# eagle65brdfile.net
KiCad netlist of a schematic drawn in EAGLE
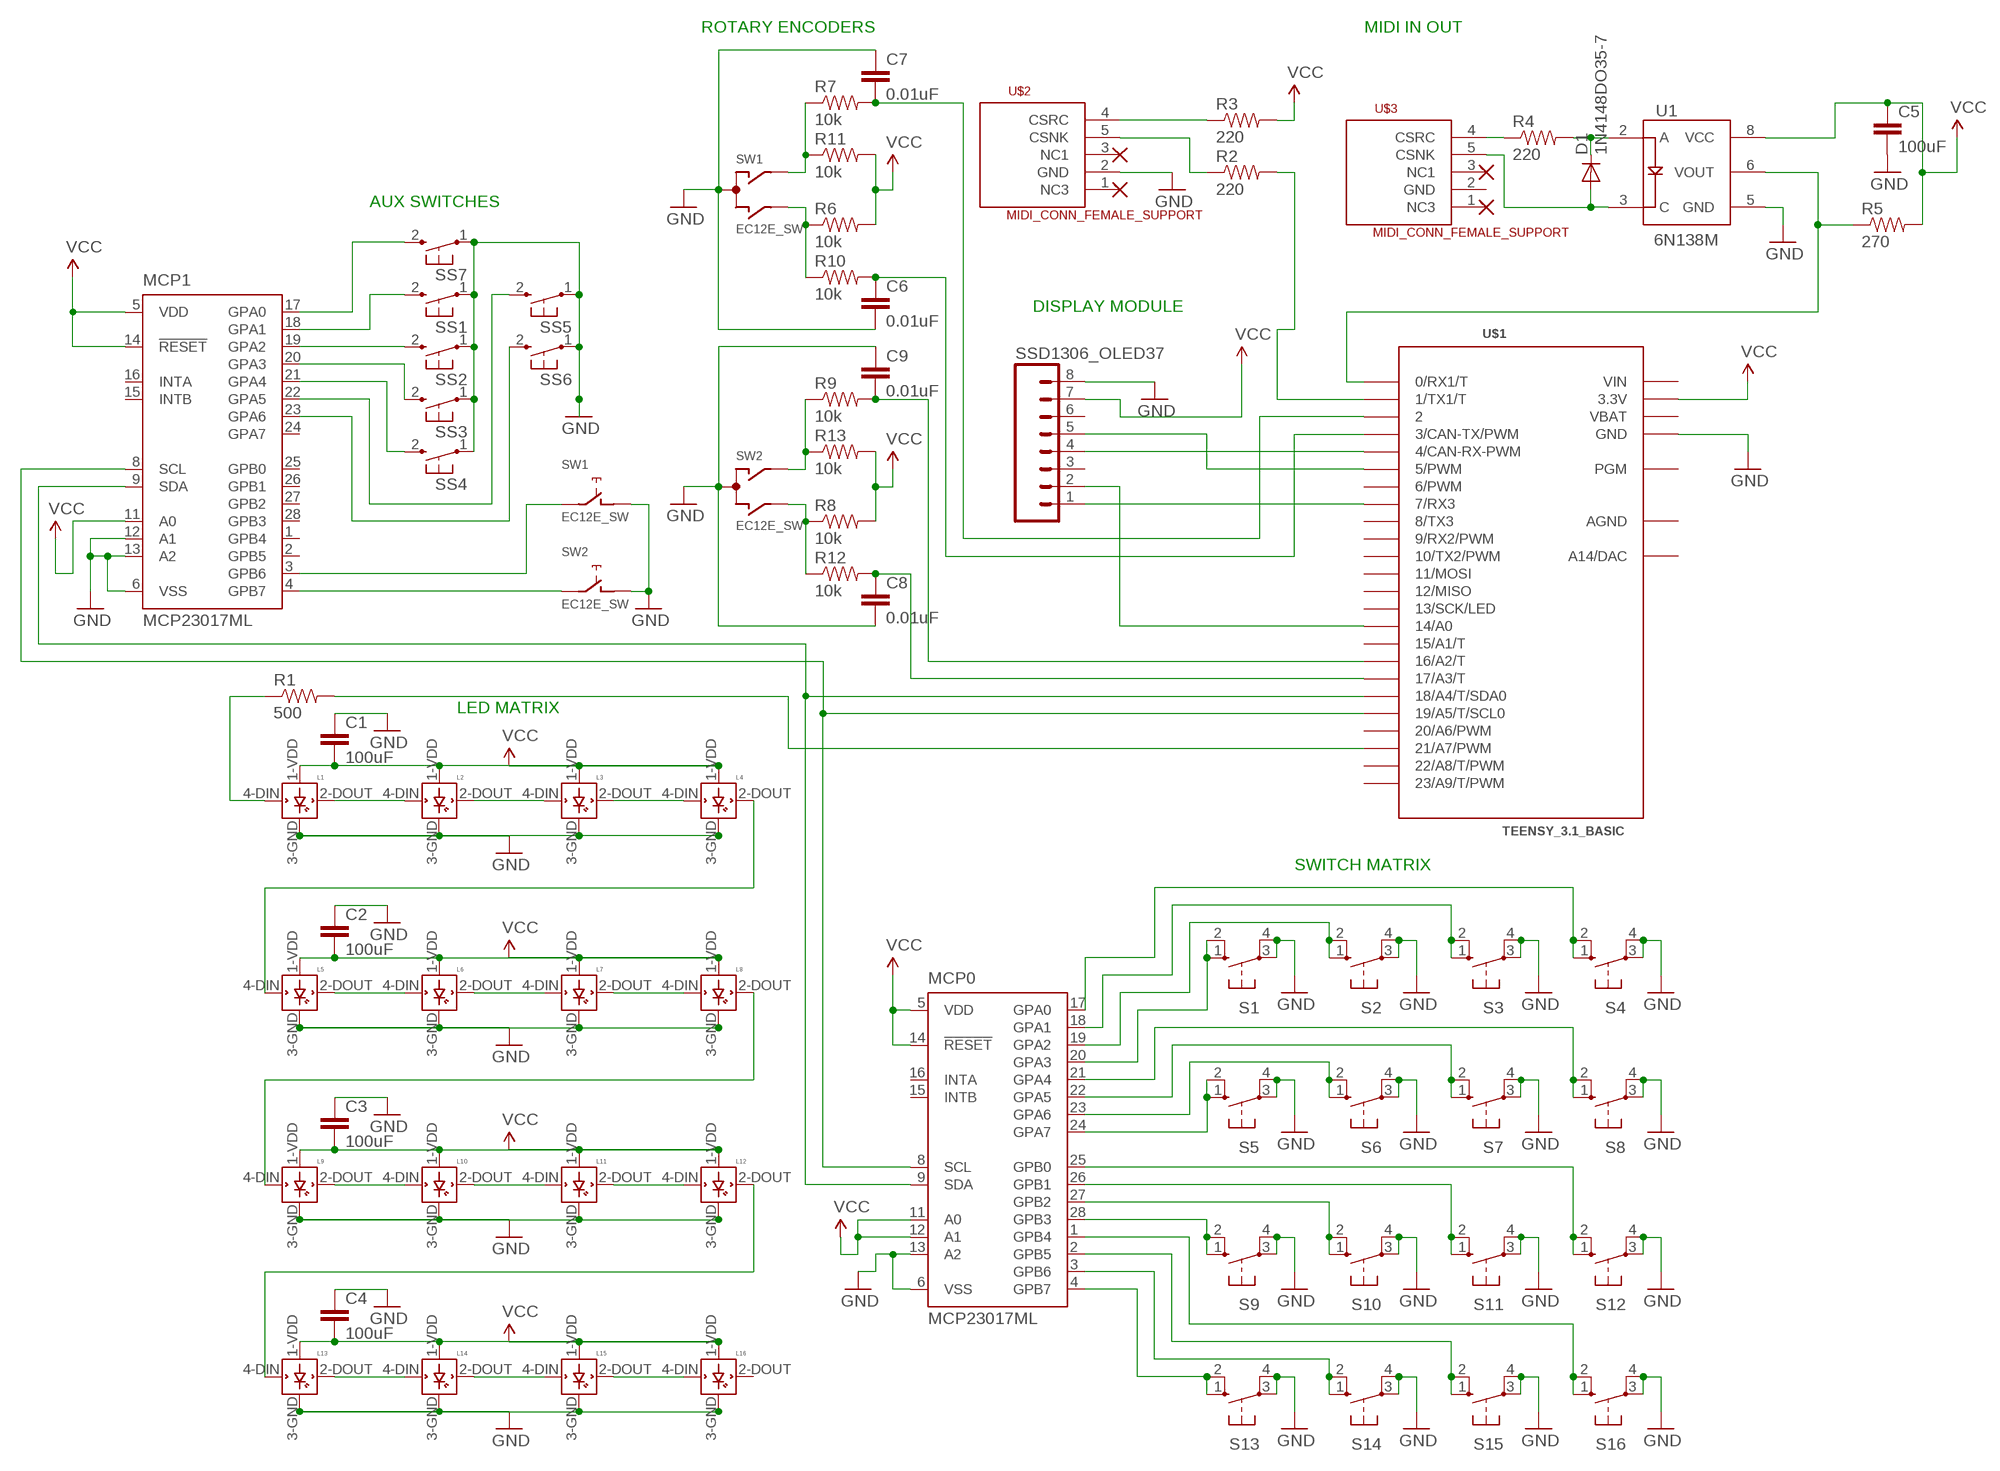
[diagram p0: schematic, sheet 1]

(export (version "E")
  (design (tool "Eeschema 10.0.6"))
  (components
    (comp (ref "C1")
      (value "100uF")
      (footprint "eagle-import:0805")
      (libsource (lib "eagle-import") (part "1.0UF-25V-+80/-20(0805)"))
    )
    (comp (ref "C2")
      (value "100uF")
      (footprint "eagle-import:0805")
      (libsource (lib "eagle-import") (part "1.0UF-25V-+80/-20(0805)"))
    )
    (comp (ref "C3")
      (value "100uF")
      (footprint "eagle-import:0805")
      (libsource (lib "eagle-import") (part "1.0UF-25V-+80/-20(0805)"))
    )
    (comp (ref "C4")
      (value "100uF")
      (footprint "eagle-import:0805")
      (libsource (lib "eagle-import") (part "1.0UF-25V-+80/-20(0805)"))
    )
    (comp (ref "C5")
      (value "100uF")
      (footprint "eagle-import:0805")
      (libsource (lib "eagle-import") (part "1.0UF-25V-+80/-20(0805)"))
    )
    (comp (ref "C6")
      (value "0.01uF")
      (footprint "eagle-import:0805")
      (libsource (lib "eagle-import") (part "1.0UF-25V-+80/-20(0805)"))
    )
    (comp (ref "C7")
      (value "0.01uF")
      (footprint "eagle-import:0805")
      (libsource (lib "eagle-import") (part "1.0UF-25V-+80/-20(0805)"))
    )
    (comp (ref "C8")
      (value "0.01uF")
      (footprint "eagle-import:0805")
      (libsource (lib "eagle-import") (part "1.0UF-25V-+80/-20(0805)"))
    )
    (comp (ref "C9")
      (value "0.01uF")
      (footprint "eagle-import:0805")
      (libsource (lib "eagle-import") (part "1.0UF-25V-+80/-20(0805)"))
    )
    (comp (ref "D1")
      (value "1N4148DO35-7")
      (footprint "eagle-import:DO35-7")
      (libsource (lib "eagle-import") (part "1N4148DO35-7"))
    )
    (comp (ref "L1")
      (value "WS2812B")
      (footprint "eagle-import:WS2812B")
      (libsource (lib "eagle-import") (part "WS2812B"))
    )
    (comp (ref "L2")
      (value "WS2812B")
      (footprint "eagle-import:WS2812B")
      (libsource (lib "eagle-import") (part "WS2812B"))
    )
    (comp (ref "L3")
      (value "WS2812B")
      (footprint "eagle-import:WS2812B")
      (libsource (lib "eagle-import") (part "WS2812B"))
    )
    (comp (ref "L4")
      (value "WS2812B")
      (footprint "eagle-import:WS2812B")
      (libsource (lib "eagle-import") (part "WS2812B"))
    )
    (comp (ref "L5")
      (value "WS2812B")
      (footprint "eagle-import:WS2812B")
      (libsource (lib "eagle-import") (part "WS2812B"))
    )
    (comp (ref "L6")
      (value "WS2812B")
      (footprint "eagle-import:WS2812B")
      (libsource (lib "eagle-import") (part "WS2812B"))
    )
    (comp (ref "L7")
      (value "WS2812B")
      (footprint "eagle-import:WS2812B")
      (libsource (lib "eagle-import") (part "WS2812B"))
    )
    (comp (ref "L8")
      (value "WS2812B")
      (footprint "eagle-import:WS2812B")
      (libsource (lib "eagle-import") (part "WS2812B"))
    )
    (comp (ref "L9")
      (value "WS2812B")
      (footprint "eagle-import:WS2812B")
      (libsource (lib "eagle-import") (part "WS2812B"))
    )
    (comp (ref "L10")
      (value "WS2812B")
      (footprint "eagle-import:WS2812B")
      (libsource (lib "eagle-import") (part "WS2812B"))
    )
    (comp (ref "L11")
      (value "WS2812B")
      (footprint "eagle-import:WS2812B")
      (libsource (lib "eagle-import") (part "WS2812B"))
    )
    (comp (ref "L12")
      (value "WS2812B")
      (footprint "eagle-import:WS2812B")
      (libsource (lib "eagle-import") (part "WS2812B"))
    )
    (comp (ref "L13")
      (value "WS2812B")
      (footprint "eagle-import:WS2812B")
      (libsource (lib "eagle-import") (part "WS2812B"))
    )
    (comp (ref "L14")
      (value "WS2812B")
      (footprint "eagle-import:WS2812B")
      (libsource (lib "eagle-import") (part "WS2812B"))
    )
    (comp (ref "L15")
      (value "WS2812B")
      (footprint "eagle-import:WS2812B")
      (libsource (lib "eagle-import") (part "WS2812B"))
    )
    (comp (ref "L16")
      (value "WS2812B")
      (footprint "eagle-import:WS2812B")
      (libsource (lib "eagle-import") (part "WS2812B"))
    )
    (comp (ref "MCP0")
      (value "MCP23017ML")
      (footprint "eagle-import:QFN28-ML_6X6MM")
      (fields (field (name "MF") "MICROCHIP") (field (name "MPN") "MCP23017-E/ML"))
      (libsource (lib "eagle-import") (part "MCP23017ML"))
    )
    (comp (ref "MCP1")
      (value "MCP23017ML")
      (footprint "eagle-import:QFN28-ML_6X6MM")
      (fields (field (name "MF") "MICROCHIP") (field (name "MPN") "MCP23017-E/ML"))
      (libsource (lib "eagle-import") (part "MCP23017ML"))
    )
    (comp (ref "R1")
      (value "500")
      (footprint "eagle-import:0805")
      (libsource (lib "eagle-import") (part "RESISTOR0805-RES"))
    )
    (comp (ref "R2")
      (value "220")
      (footprint "eagle-import:0805")
      (libsource (lib "eagle-import") (part "RESISTOR0805-RES"))
    )
    (comp (ref "R3")
      (value "220")
      (footprint "eagle-import:0805")
      (libsource (lib "eagle-import") (part "RESISTOR0805-RES"))
    )
    (comp (ref "R4")
      (value "220")
      (footprint "eagle-import:0805")
      (libsource (lib "eagle-import") (part "RESISTOR0805-RES"))
    )
    (comp (ref "R5")
      (value "270")
      (footprint "eagle-import:0805")
      (libsource (lib "eagle-import") (part "RESISTOR0805-RES"))
    )
    (comp (ref "R6")
      (value "10k")
      (footprint "eagle-import:0805")
      (libsource (lib "eagle-import") (part "RESISTOR0805-RES"))
    )
    (comp (ref "R7")
      (value "10k")
      (footprint "eagle-import:0805")
      (libsource (lib "eagle-import") (part "RESISTOR0805-RES"))
    )
    (comp (ref "R8")
      (value "10k")
      (footprint "eagle-import:0805")
      (libsource (lib "eagle-import") (part "RESISTOR0805-RES"))
    )
    (comp (ref "R9")
      (value "10k")
      (footprint "eagle-import:0805")
      (libsource (lib "eagle-import") (part "RESISTOR0805-RES"))
    )
    (comp (ref "R10")
      (value "10k")
      (footprint "eagle-import:0805")
      (libsource (lib "eagle-import") (part "RESISTOR0805-RES"))
    )
    (comp (ref "R11")
      (value "10k")
      (footprint "eagle-import:0805")
      (libsource (lib "eagle-import") (part "RESISTOR0805-RES"))
    )
    (comp (ref "R12")
      (value "10k")
      (footprint "eagle-import:0805")
      (libsource (lib "eagle-import") (part "RESISTOR0805-RES"))
    )
    (comp (ref "R13")
      (value "10k")
      (footprint "eagle-import:0805")
      (libsource (lib "eagle-import") (part "RESISTOR0805-RES"))
    )
    (comp (ref "S1")
      (value "10-XX")
      (footprint "eagle-import:B3F-10XX")
      (fields (field (name "MPN") "B3F-1000"))
      (libsource (lib "eagle-import") (part "10-XX"))
    )
    (comp (ref "S2")
      (value "10-XX")
      (footprint "eagle-import:B3F-10XX")
      (fields (field (name "MPN") "B3F-1000"))
      (libsource (lib "eagle-import") (part "10-XX"))
    )
    (comp (ref "S3")
      (value "10-XX")
      (footprint "eagle-import:B3F-10XX")
      (fields (field (name "MPN") "B3F-1000"))
      (libsource (lib "eagle-import") (part "10-XX"))
    )
    (comp (ref "S4")
      (value "10-XX")
      (footprint "eagle-import:B3F-10XX")
      (fields (field (name "MPN") "B3F-1000"))
      (libsource (lib "eagle-import") (part "10-XX"))
    )
    (comp (ref "S5")
      (value "10-XX")
      (footprint "eagle-import:B3F-10XX")
      (fields (field (name "MPN") "B3F-1000"))
      (libsource (lib "eagle-import") (part "10-XX"))
    )
    (comp (ref "S6")
      (value "10-XX")
      (footprint "eagle-import:B3F-10XX")
      (fields (field (name "MPN") "B3F-1000"))
      (libsource (lib "eagle-import") (part "10-XX"))
    )
    (comp (ref "S7")
      (value "10-XX")
      (footprint "eagle-import:B3F-10XX")
      (fields (field (name "MPN") "B3F-1000"))
      (libsource (lib "eagle-import") (part "10-XX"))
    )
    (comp (ref "S8")
      (value "10-XX")
      (footprint "eagle-import:B3F-10XX")
      (fields (field (name "MPN") "B3F-1000"))
      (libsource (lib "eagle-import") (part "10-XX"))
    )
    (comp (ref "S9")
      (value "10-XX")
      (footprint "eagle-import:B3F-10XX")
      (fields (field (name "MPN") "B3F-1000"))
      (libsource (lib "eagle-import") (part "10-XX"))
    )
    (comp (ref "S10")
      (value "10-XX")
      (footprint "eagle-import:B3F-10XX")
      (fields (field (name "MPN") "B3F-1000"))
      (libsource (lib "eagle-import") (part "10-XX"))
    )
    (comp (ref "S11")
      (value "10-XX")
      (footprint "eagle-import:B3F-10XX")
      (fields (field (name "MPN") "B3F-1000"))
      (libsource (lib "eagle-import") (part "10-XX"))
    )
    (comp (ref "S12")
      (value "10-XX")
      (footprint "eagle-import:B3F-10XX")
      (fields (field (name "MPN") "B3F-1000"))
      (libsource (lib "eagle-import") (part "10-XX"))
    )
    (comp (ref "S13")
      (value "10-XX")
      (footprint "eagle-import:B3F-10XX")
      (fields (field (name "MPN") "B3F-1000"))
      (libsource (lib "eagle-import") (part "10-XX"))
    )
    (comp (ref "S14")
      (value "10-XX")
      (footprint "eagle-import:B3F-10XX")
      (fields (field (name "MPN") "B3F-1000"))
      (libsource (lib "eagle-import") (part "10-XX"))
    )
    (comp (ref "S15")
      (value "10-XX")
      (footprint "eagle-import:B3F-10XX")
      (fields (field (name "MPN") "B3F-1000"))
      (libsource (lib "eagle-import") (part "10-XX"))
    )
    (comp (ref "S16")
      (value "10-XX")
      (footprint "eagle-import:B3F-10XX")
      (fields (field (name "MPN") "B3F-1000"))
      (libsource (lib "eagle-import") (part "10-XX"))
    )
    (comp (ref "SS1")
      (value "10-XX6MMSLIM")
      (footprint "eagle-import:B3F-10XX")
      (libsource (lib "eagle-import") (part "10-XX6MMSLIM"))
    )
    (comp (ref "SS2")
      (value "10-XX6MMSLIM")
      (footprint "eagle-import:B3F-10XX")
      (libsource (lib "eagle-import") (part "10-XX6MMSLIM"))
    )
    (comp (ref "SS3")
      (value "10-XX6MMSLIM")
      (footprint "eagle-import:B3F-10XX")
      (libsource (lib "eagle-import") (part "10-XX6MMSLIM"))
    )
    (comp (ref "SS4")
      (value "10-XX6MMSLIM")
      (footprint "eagle-import:B3F-10XX")
      (libsource (lib "eagle-import") (part "10-XX6MMSLIM"))
    )
    (comp (ref "SS5")
      (value "10-XX6MMSLIM")
      (footprint "eagle-import:B3F-10XX")
      (libsource (lib "eagle-import") (part "10-XX6MMSLIM"))
    )
    (comp (ref "SS6")
      (value "10-XX6MMSLIM")
      (footprint "eagle-import:B3F-10XX")
      (libsource (lib "eagle-import") (part "10-XX6MMSLIM"))
    )
    (comp (ref "SS7")
      (value "10-XX6MMSLIM")
      (footprint "eagle-import:B3F-10XX")
      (libsource (lib "eagle-import") (part "10-XX6MMSLIM"))
    )
    (comp (ref "SSD1306_OLED37")
      (value "M08")
      (footprint "eagle-import:1X08_ROUND")
      (libsource (lib "eagle-import") (part "M08"))
    )
    (comp (ref "SW1")
      (value "EC12E_SW")
      (footprint "eagle-import:ALPS_EC12E_SW")
      (fields (field (name "MPN") "EC12E2424407"))
      (libsource (lib "eagle-import") (part "EC12E_SW"))
    )
    (comp (ref "SW2")
      (value "EC12E_SW")
      (footprint "eagle-import:ALPS_EC12E_SW")
      (fields (field (name "MPN") "EC12E2424407"))
      (libsource (lib "eagle-import") (part "EC12E_SW"))
    )
    (comp (ref "U$1")
      (value "TEENSY_3.1_BASIC")
      (footprint "eagle-import:TEENSY_3.1_BASIC")
      (libsource (lib "eagle-import") (part "TEENSY_3.1_BASIC"))
    )
    (comp (ref "U$2")
      (value "MIDI_CONN_FEMALE_SUPPORT")
      (footprint "eagle-import:DIN_5_FEMALE_SUPPORT")
      (libsource (lib "eagle-import") (part "MIDI_CONN_FEMALE_SUPPORT"))
    )
    (comp (ref "U$3")
      (value "MIDI_CONN_FEMALE_SUPPORT")
      (footprint "eagle-import:DIN_5_FEMALE_SUPPORT")
      (libsource (lib "eagle-import") (part "MIDI_CONN_FEMALE_SUPPORT"))
    )
    (comp (ref "U1")
      (value "6N138M")
      (footprint "eagle-import:8-SMD")
      (libsource (lib "eagle-import") (part "OPTO_DARL_6N138S"))
    )
  )
  (nets
    (net (code "1") (name "/AGND") (class "Default")
      (node (ref "U$1") (pin "AGND") (pinfunction "AGND_AGND") (pintype "power_in"))
    )
    (net (code "2") (name "/VBAT") (class "Default")
      (node (ref "U$1") (pin "VBAT") (pinfunction "VBAT_VBAT") (pintype "power_in"))
    )
    (net (code "3") (name "/VIN") (class "Default")
      (node (ref "U$1") (pin "VIN") (pinfunction "VIN_VIN") (pintype "power_in"))
    )
    (net (code "4") (name "GND") (class "Default")
      (node (ref "C1") (pin "1") (pinfunction "1_1") (pintype "passive"))
      (node (ref "C2") (pin "1") (pinfunction "1_1") (pintype "passive"))
      (node (ref "C3") (pin "1") (pinfunction "1_1") (pintype "passive"))
      (node (ref "C4") (pin "1") (pinfunction "1_1") (pintype "passive"))
      (node (ref "C5") (pin "2") (pinfunction "2_2") (pintype "passive"))
      (node (ref "C6") (pin "2") (pinfunction "2_2") (pintype "passive"))
      (node (ref "C7") (pin "1") (pinfunction "1_1") (pintype "passive"))
      (node (ref "C8") (pin "2") (pinfunction "2_2") (pintype "passive"))
      (node (ref "C9") (pin "1") (pinfunction "1_1") (pintype "passive"))
      (node (ref "L1") (pin "3-GND") (pinfunction "GND_3-GND") (pintype "bidirectional"))
      (node (ref "L10") (pin "3-GND") (pinfunction "GND_3-GND") (pintype "bidirectional"))
      (node (ref "L11") (pin "3-GND") (pinfunction "GND_3-GND") (pintype "bidirectional"))
      (node (ref "L12") (pin "3-GND") (pinfunction "GND_3-GND") (pintype "bidirectional"))
      (node (ref "L13") (pin "3-GND") (pinfunction "GND_3-GND") (pintype "bidirectional"))
      (node (ref "L14") (pin "3-GND") (pinfunction "GND_3-GND") (pintype "bidirectional"))
      (node (ref "L15") (pin "3-GND") (pinfunction "GND_3-GND") (pintype "bidirectional"))
      (node (ref "L16") (pin "3-GND") (pinfunction "GND_3-GND") (pintype "bidirectional"))
      (node (ref "L2") (pin "3-GND") (pinfunction "GND_3-GND") (pintype "bidirectional"))
      (node (ref "L3") (pin "3-GND") (pinfunction "GND_3-GND") (pintype "bidirectional"))
      (node (ref "L4") (pin "3-GND") (pinfunction "GND_3-GND") (pintype "bidirectional"))
      (node (ref "L5") (pin "3-GND") (pinfunction "GND_3-GND") (pintype "bidirectional"))
      (node (ref "L6") (pin "3-GND") (pinfunction "GND_3-GND") (pintype "bidirectional"))
      (node (ref "L7") (pin "3-GND") (pinfunction "GND_3-GND") (pintype "bidirectional"))
      (node (ref "L8") (pin "3-GND") (pinfunction "GND_3-GND") (pintype "bidirectional"))
      (node (ref "L9") (pin "3-GND") (pinfunction "GND_3-GND") (pintype "bidirectional"))
      (node (ref "MCP0") (pin "13") (pinfunction "A2_13") (pintype "input"))
      (node (ref "MCP0") (pin "6") (pinfunction "VSS_6") (pintype "power_in"))
      (node (ref "MCP1") (pin "12") (pinfunction "A1_12") (pintype "input"))
      (node (ref "MCP1") (pin "13") (pinfunction "A2_13") (pintype "input"))
      (node (ref "MCP1") (pin "6") (pinfunction "VSS_6") (pintype "power_in"))
      (node (ref "S1") (pin "3") (pinfunction "P_3") (pintype "passive"))
      (node (ref "S1") (pin "4") (pinfunction "P1_4") (pintype "passive"))
      (node (ref "S10") (pin "3") (pinfunction "P_3") (pintype "passive"))
      (node (ref "S10") (pin "4") (pinfunction "P1_4") (pintype "passive"))
      (node (ref "S11") (pin "3") (pinfunction "P_3") (pintype "passive"))
      (node (ref "S11") (pin "4") (pinfunction "P1_4") (pintype "passive"))
      (node (ref "S12") (pin "3") (pinfunction "P_3") (pintype "passive"))
      (node (ref "S12") (pin "4") (pinfunction "P1_4") (pintype "passive"))
      (node (ref "S13") (pin "3") (pinfunction "P_3") (pintype "passive"))
      (node (ref "S13") (pin "4") (pinfunction "P1_4") (pintype "passive"))
      (node (ref "S14") (pin "3") (pinfunction "P_3") (pintype "passive"))
      (node (ref "S14") (pin "4") (pinfunction "P1_4") (pintype "passive"))
      (node (ref "S15") (pin "3") (pinfunction "P_3") (pintype "passive"))
      (node (ref "S15") (pin "4") (pinfunction "P1_4") (pintype "passive"))
      (node (ref "S16") (pin "3") (pinfunction "P_3") (pintype "passive"))
      (node (ref "S16") (pin "4") (pinfunction "P1_4") (pintype "passive"))
      (node (ref "S2") (pin "3") (pinfunction "P_3") (pintype "passive"))
      (node (ref "S2") (pin "4") (pinfunction "P1_4") (pintype "passive"))
      (node (ref "S3") (pin "3") (pinfunction "P_3") (pintype "passive"))
      (node (ref "S3") (pin "4") (pinfunction "P1_4") (pintype "passive"))
      (node (ref "S4") (pin "3") (pinfunction "P_3") (pintype "passive"))
      (node (ref "S4") (pin "4") (pinfunction "P1_4") (pintype "passive"))
      (node (ref "S5") (pin "3") (pinfunction "P_3") (pintype "passive"))
      (node (ref "S5") (pin "4") (pinfunction "P1_4") (pintype "passive"))
      (node (ref "S6") (pin "3") (pinfunction "P_3") (pintype "passive"))
      (node (ref "S6") (pin "4") (pinfunction "P1_4") (pintype "passive"))
      (node (ref "S7") (pin "3") (pinfunction "P_3") (pintype "passive"))
      (node (ref "S7") (pin "4") (pinfunction "P1_4") (pintype "passive"))
      (node (ref "S8") (pin "3") (pinfunction "P_3") (pintype "passive"))
      (node (ref "S8") (pin "4") (pinfunction "P1_4") (pintype "passive"))
      (node (ref "S9") (pin "3") (pinfunction "P_3") (pintype "passive"))
      (node (ref "S9") (pin "4") (pinfunction "P1_4") (pintype "passive"))
      (node (ref "SS1") (pin "1") (pinfunction "P1_1") (pintype "passive"))
      (node (ref "SS2") (pin "1") (pinfunction "P1_1") (pintype "passive"))
      (node (ref "SS3") (pin "1") (pinfunction "P1_1") (pintype "passive"))
      (node (ref "SS4") (pin "1") (pinfunction "P1_1") (pintype "passive"))
      (node (ref "SS5") (pin "1") (pinfunction "P1_1") (pintype "passive"))
      (node (ref "SS6") (pin "1") (pinfunction "P1_1") (pintype "passive"))
      (node (ref "SS7") (pin "1") (pinfunction "P1_1") (pintype "passive"))
      (node (ref "SSD1306_OLED37") (pin "8") (pinfunction "8_8") (pintype "passive"))
      (node (ref "SW1") (pin "C") (pinfunction "C_C") (pintype "passive"))
      (node (ref "SW1") (pin "D") (pinfunction "1_D") (pintype "passive"))
      (node (ref "SW2") (pin "C") (pinfunction "C_C") (pintype "passive"))
      (node (ref "SW2") (pin "D") (pinfunction "1_D") (pintype "passive"))
      (node (ref "U$1") (pin "GND") (pinfunction "GND_GND") (pintype "power_in"))
      (node (ref "U$1") (pin "GND1") (pinfunction "GND_GND1") (pintype "power_in"))
      (node (ref "U$2") (pin "2") (pinfunction "GND_2") (pintype "bidirectional"))
      (node (ref "U1") (pin "5") (pinfunction "GND_5") (pintype "bidirectional"))
    )
    (net (code "5") (name "Net-(C7-Pad2)") (class "Default")
      (node (ref "C7") (pin "2") (pinfunction "2_2") (pintype "passive"))
      (node (ref "R7") (pin "2") (pinfunction "2_2") (pintype "passive"))
      (node (ref "U$1") (pin "2") (pinfunction "2_2") (pintype "bidirectional"))
    )
    (net (code "6") (name "Net-(L1-DIN)") (class "Default")
      (node (ref "L1") (pin "4-DIN") (pinfunction "DIN_4-DIN") (pintype "input"))
      (node (ref "R1") (pin "1") (pinfunction "1_1") (pintype "passive"))
    )
    (net (code "7") (name "Net-(L1-DOUT)") (class "Default")
      (node (ref "L1") (pin "2-DOUT") (pinfunction "DOUT_2-DOUT") (pintype "output"))
      (node (ref "L2") (pin "4-DIN") (pinfunction "DIN_4-DIN") (pintype "input"))
    )
    (net (code "8") (name "Net-(L2-DOUT)") (class "Default")
      (node (ref "L2") (pin "2-DOUT") (pinfunction "DOUT_2-DOUT") (pintype "output"))
      (node (ref "L3") (pin "4-DIN") (pinfunction "DIN_4-DIN") (pintype "input"))
    )
    (net (code "9") (name "Net-(L3-DOUT)") (class "Default")
      (node (ref "L3") (pin "2-DOUT") (pinfunction "DOUT_2-DOUT") (pintype "output"))
      (node (ref "L4") (pin "4-DIN") (pinfunction "DIN_4-DIN") (pintype "input"))
    )
    (net (code "10") (name "Net-(L4-DOUT)") (class "Default")
      (node (ref "L4") (pin "2-DOUT") (pinfunction "DOUT_2-DOUT") (pintype "output"))
      (node (ref "L5") (pin "4-DIN") (pinfunction "DIN_4-DIN") (pintype "input"))
    )
    (net (code "11") (name "Net-(L5-DOUT)") (class "Default")
      (node (ref "L5") (pin "2-DOUT") (pinfunction "DOUT_2-DOUT") (pintype "output"))
      (node (ref "L6") (pin "4-DIN") (pinfunction "DIN_4-DIN") (pintype "input"))
    )
    (net (code "12") (name "Net-(L6-DOUT)") (class "Default")
      (node (ref "L6") (pin "2-DOUT") (pinfunction "DOUT_2-DOUT") (pintype "output"))
      (node (ref "L7") (pin "4-DIN") (pinfunction "DIN_4-DIN") (pintype "input"))
    )
    (net (code "13") (name "Net-(L7-DOUT)") (class "Default")
      (node (ref "L7") (pin "2-DOUT") (pinfunction "DOUT_2-DOUT") (pintype "output"))
      (node (ref "L8") (pin "4-DIN") (pinfunction "DIN_4-DIN") (pintype "input"))
    )
    (net (code "14") (name "Net-(L8-DOUT)") (class "Default")
      (node (ref "L8") (pin "2-DOUT") (pinfunction "DOUT_2-DOUT") (pintype "output"))
      (node (ref "L9") (pin "4-DIN") (pinfunction "DIN_4-DIN") (pintype "input"))
    )
    (net (code "15") (name "Net-(L10-DIN)") (class "Default")
      (node (ref "L10") (pin "4-DIN") (pinfunction "DIN_4-DIN") (pintype "input"))
      (node (ref "L9") (pin "2-DOUT") (pinfunction "DOUT_2-DOUT") (pintype "output"))
    )
    (net (code "16") (name "Net-(L10-DOUT)") (class "Default")
      (node (ref "L10") (pin "2-DOUT") (pinfunction "DOUT_2-DOUT") (pintype "output"))
      (node (ref "L11") (pin "4-DIN") (pinfunction "DIN_4-DIN") (pintype "input"))
    )
    (net (code "17") (name "Net-(L11-DOUT)") (class "Default")
      (node (ref "L11") (pin "2-DOUT") (pinfunction "DOUT_2-DOUT") (pintype "output"))
      (node (ref "L12") (pin "4-DIN") (pinfunction "DIN_4-DIN") (pintype "input"))
    )
    (net (code "18") (name "Net-(L12-DOUT)") (class "Default")
      (node (ref "L12") (pin "2-DOUT") (pinfunction "DOUT_2-DOUT") (pintype "output"))
      (node (ref "L13") (pin "4-DIN") (pinfunction "DIN_4-DIN") (pintype "input"))
    )
    (net (code "19") (name "Net-(L13-DOUT)") (class "Default")
      (node (ref "L13") (pin "2-DOUT") (pinfunction "DOUT_2-DOUT") (pintype "output"))
      (node (ref "L14") (pin "4-DIN") (pinfunction "DIN_4-DIN") (pintype "input"))
    )
    (net (code "20") (name "Net-(L14-DOUT)") (class "Default")
      (node (ref "L14") (pin "2-DOUT") (pinfunction "DOUT_2-DOUT") (pintype "output"))
      (node (ref "L15") (pin "4-DIN") (pinfunction "DIN_4-DIN") (pintype "input"))
    )
    (net (code "21") (name "Net-(L15-DOUT)") (class "Default")
      (node (ref "L15") (pin "2-DOUT") (pinfunction "DOUT_2-DOUT") (pintype "output"))
      (node (ref "L16") (pin "4-DIN") (pinfunction "DIN_4-DIN") (pintype "input"))
    )
    (net (code "22") (name "Net-(MCP0-GPA0)") (class "Default")
      (node (ref "MCP0") (pin "17") (pinfunction "GPA0_17") (pintype "bidirectional"))
      (node (ref "S4") (pin "1") (pinfunction "S_1") (pintype "passive"))
      (node (ref "S4") (pin "2") (pinfunction "S1_2") (pintype "passive"))
    )
    (net (code "23") (name "Net-(MCP0-GPA1)") (class "Default")
      (node (ref "MCP0") (pin "18") (pinfunction "GPA1_18") (pintype "bidirectional"))
      (node (ref "S3") (pin "1") (pinfunction "S_1") (pintype "passive"))
      (node (ref "S3") (pin "2") (pinfunction "S1_2") (pintype "passive"))
    )
    (net (code "24") (name "Net-(MCP0-GPA2)") (class "Default")
      (node (ref "MCP0") (pin "19") (pinfunction "GPA2_19") (pintype "bidirectional"))
      (node (ref "S2") (pin "1") (pinfunction "S_1") (pintype "passive"))
      (node (ref "S2") (pin "2") (pinfunction "S1_2") (pintype "passive"))
    )
    (net (code "25") (name "Net-(MCP0-GPA3)") (class "Default")
      (node (ref "MCP0") (pin "20") (pinfunction "GPA3_20") (pintype "bidirectional"))
      (node (ref "S1") (pin "1") (pinfunction "S_1") (pintype "passive"))
      (node (ref "S1") (pin "2") (pinfunction "S1_2") (pintype "passive"))
    )
    (net (code "26") (name "Net-(MCP0-GPA4)") (class "Default")
      (node (ref "MCP0") (pin "21") (pinfunction "GPA4_21") (pintype "bidirectional"))
      (node (ref "S8") (pin "1") (pinfunction "S_1") (pintype "passive"))
      (node (ref "S8") (pin "2") (pinfunction "S1_2") (pintype "passive"))
    )
    (net (code "27") (name "Net-(MCP0-GPA5)") (class "Default")
      (node (ref "MCP0") (pin "22") (pinfunction "GPA5_22") (pintype "bidirectional"))
      (node (ref "S7") (pin "1") (pinfunction "S_1") (pintype "passive"))
      (node (ref "S7") (pin "2") (pinfunction "S1_2") (pintype "passive"))
    )
    (net (code "28") (name "Net-(MCP0-GPA6)") (class "Default")
      (node (ref "MCP0") (pin "23") (pinfunction "GPA6_23") (pintype "bidirectional"))
      (node (ref "S6") (pin "1") (pinfunction "S_1") (pintype "passive"))
      (node (ref "S6") (pin "2") (pinfunction "S1_2") (pintype "passive"))
    )
    (net (code "29") (name "Net-(MCP0-GPA7)") (class "Default")
      (node (ref "MCP0") (pin "24") (pinfunction "GPA7_24") (pintype "bidirectional"))
      (node (ref "S5") (pin "1") (pinfunction "S_1") (pintype "passive"))
      (node (ref "S5") (pin "2") (pinfunction "S1_2") (pintype "passive"))
    )
    (net (code "30") (name "Net-(MCP0-GPB0)") (class "Default")
      (node (ref "MCP0") (pin "25") (pinfunction "GPB0_25") (pintype "bidirectional"))
      (node (ref "S12") (pin "1") (pinfunction "S_1") (pintype "passive"))
      (node (ref "S12") (pin "2") (pinfunction "S1_2") (pintype "passive"))
    )
    (net (code "31") (name "Net-(MCP0-GPB1)") (class "Default")
      (node (ref "MCP0") (pin "26") (pinfunction "GPB1_26") (pintype "bidirectional"))
      (node (ref "S11") (pin "1") (pinfunction "S_1") (pintype "passive"))
      (node (ref "S11") (pin "2") (pinfunction "S1_2") (pintype "passive"))
    )
    (net (code "32") (name "Net-(MCP0-GPB2)") (class "Default")
      (node (ref "MCP0") (pin "27") (pinfunction "GPB2_27") (pintype "bidirectional"))
      (node (ref "S10") (pin "1") (pinfunction "S_1") (pintype "passive"))
      (node (ref "S10") (pin "2") (pinfunction "S1_2") (pintype "passive"))
    )
    (net (code "33") (name "Net-(MCP0-GPB3)") (class "Default")
      (node (ref "MCP0") (pin "28") (pinfunction "GPB3_28") (pintype "bidirectional"))
      (node (ref "S9") (pin "1") (pinfunction "S_1") (pintype "passive"))
      (node (ref "S9") (pin "2") (pinfunction "S1_2") (pintype "passive"))
    )
    (net (code "34") (name "Net-(MCP0-GPB4)") (class "Default")
      (node (ref "MCP0") (pin "1") (pinfunction "GPB4_1") (pintype "bidirectional"))
      (node (ref "S16") (pin "1") (pinfunction "S_1") (pintype "passive"))
      (node (ref "S16") (pin "2") (pinfunction "S1_2") (pintype "passive"))
    )
    (net (code "35") (name "Net-(MCP0-GPB5)") (class "Default")
      (node (ref "MCP0") (pin "2") (pinfunction "GPB5_2") (pintype "bidirectional"))
      (node (ref "S15") (pin "1") (pinfunction "S_1") (pintype "passive"))
      (node (ref "S15") (pin "2") (pinfunction "S1_2") (pintype "passive"))
    )
    (net (code "36") (name "Net-(MCP0-GPB6)") (class "Default")
      (node (ref "MCP0") (pin "3") (pinfunction "GPB6_3") (pintype "bidirectional"))
      (node (ref "S14") (pin "1") (pinfunction "S_1") (pintype "passive"))
      (node (ref "S14") (pin "2") (pinfunction "S1_2") (pintype "passive"))
    )
    (net (code "37") (name "Net-(MCP0-GPB7)") (class "Default")
      (node (ref "MCP0") (pin "4") (pinfunction "GPB7_4") (pintype "bidirectional"))
      (node (ref "S13") (pin "1") (pinfunction "S_1") (pintype "passive"))
      (node (ref "S13") (pin "2") (pinfunction "S1_2") (pintype "passive"))
    )
    (net (code "38") (name "Net-(MCP0-SCL)") (class "Default")
      (node (ref "MCP0") (pin "8") (pinfunction "SCL_8") (pintype "input"))
      (node (ref "MCP1") (pin "8") (pinfunction "SCL_8") (pintype "input"))
      (node (ref "U$1") (pin "19/A5") (pinfunction "19/A5/T/SCL0_19/A5") (pintype "bidirectional"))
    )
    (net (code "39") (name "Net-(MCP0-SDA)") (class "Default")
      (node (ref "MCP0") (pin "9") (pinfunction "SDA_9") (pintype "bidirectional"))
      (node (ref "MCP1") (pin "9") (pinfunction "SDA_9") (pintype "bidirectional"))
      (node (ref "U$1") (pin "18/A4") (pinfunction "18/A4/T/SDA0_18/A4") (pintype "bidirectional"))
    )
    (net (code "40") (name "Net-(MCP1-GPA0)") (class "Default")
      (node (ref "MCP1") (pin "17") (pinfunction "GPA0_17") (pintype "bidirectional"))
      (node (ref "SS7") (pin "2") (pinfunction "S1_2") (pintype "passive"))
    )
    (net (code "41") (name "Net-(MCP1-GPA1)") (class "Default")
      (node (ref "MCP1") (pin "18") (pinfunction "GPA1_18") (pintype "bidirectional"))
      (node (ref "SS1") (pin "2") (pinfunction "S1_2") (pintype "passive"))
    )
    (net (code "42") (name "Net-(MCP1-GPA2)") (class "Default")
      (node (ref "MCP1") (pin "19") (pinfunction "GPA2_19") (pintype "bidirectional"))
      (node (ref "SS2") (pin "2") (pinfunction "S1_2") (pintype "passive"))
    )
    (net (code "43") (name "Net-(MCP1-GPA3)") (class "Default")
      (node (ref "MCP1") (pin "20") (pinfunction "GPA3_20") (pintype "bidirectional"))
      (node (ref "SS3") (pin "2") (pinfunction "S1_2") (pintype "passive"))
    )
    (net (code "44") (name "Net-(MCP1-GPA4)") (class "Default")
      (node (ref "MCP1") (pin "21") (pinfunction "GPA4_21") (pintype "bidirectional"))
      (node (ref "SS4") (pin "2") (pinfunction "S1_2") (pintype "passive"))
    )
    (net (code "45") (name "Net-(MCP1-GPA5)") (class "Default")
      (node (ref "MCP1") (pin "22") (pinfunction "GPA5_22") (pintype "bidirectional"))
      (node (ref "SS5") (pin "2") (pinfunction "S1_2") (pintype "passive"))
    )
    (net (code "46") (name "Net-(MCP1-GPA6)") (class "Default")
      (node (ref "MCP1") (pin "23") (pinfunction "GPA6_23") (pintype "bidirectional"))
      (node (ref "SS6") (pin "2") (pinfunction "S1_2") (pintype "passive"))
    )
    (net (code "47") (name "Net-(MCP1-GPB6)") (class "Default")
      (node (ref "MCP1") (pin "3") (pinfunction "GPB6_3") (pintype "bidirectional"))
      (node (ref "SW1") (pin "E") (pinfunction "2_E") (pintype "passive"))
    )
    (net (code "48") (name "Net-(MCP1-GPB7)") (class "Default")
      (node (ref "MCP1") (pin "4") (pinfunction "GPB7_4") (pintype "bidirectional"))
      (node (ref "SW2") (pin "E") (pinfunction "2_E") (pintype "passive"))
    )
    (net (code "49") (name "Net-(R10-Pad1)") (class "Default")
      (node (ref "R10") (pin "1") (pinfunction "1_1") (pintype "passive"))
      (node (ref "R6") (pin "1") (pinfunction "1_1") (pintype "passive"))
      (node (ref "SW1") (pin "B") (pinfunction "B_B") (pintype "passive"))
    )
    (net (code "50") (name "Net-(R11-Pad1)") (class "Default")
      (node (ref "R11") (pin "1") (pinfunction "1_1") (pintype "passive"))
      (node (ref "R7") (pin "1") (pinfunction "1_1") (pintype "passive"))
      (node (ref "SW1") (pin "A") (pinfunction "A_A") (pintype "passive"))
    )
    (net (code "51") (name "Net-(R12-Pad1)") (class "Default")
      (node (ref "R12") (pin "1") (pinfunction "1_1") (pintype "passive"))
      (node (ref "R8") (pin "1") (pinfunction "1_1") (pintype "passive"))
      (node (ref "SW2") (pin "B") (pinfunction "B_B") (pintype "passive"))
    )
    (net (code "52") (name "Net-(R13-Pad1)") (class "Default")
      (node (ref "R13") (pin "1") (pinfunction "1_1") (pintype "passive"))
      (node (ref "R9") (pin "1") (pinfunction "1_1") (pintype "passive"))
      (node (ref "SW2") (pin "A") (pinfunction "A_A") (pintype "passive"))
    )
    (net (code "53") (name "Net-(SSD1306_OLED37-Pad2)") (class "Default")
      (node (ref "SSD1306_OLED37") (pin "2") (pinfunction "2_2") (pintype "passive"))
      (node (ref "U$1") (pin "14/A0") (pinfunction "14/A0_14/A0") (pintype "bidirectional"))
    )
    (net (code "54") (name "Net-(U$1-0{slash}RX1{slash}T)") (class "Default")
      (node (ref "R5") (pin "1") (pinfunction "1_1") (pintype "passive"))
      (node (ref "U$1") (pin "0") (pinfunction "0/RX1/T_0") (pintype "bidirectional"))
      (node (ref "U1") (pin "6") (pinfunction "VOUT_6") (pintype "bidirectional"))
    )
    (net (code "55") (name "Net-(U$1-1{slash}TX1{slash}T)") (class "Default")
      (node (ref "R2") (pin "2") (pinfunction "2_2") (pintype "passive"))
      (node (ref "U$1") (pin "1") (pinfunction "1/TX1/T_1") (pintype "bidirectional"))
    )
    (net (code "56") (name "Net-(U$1-3{slash}CAN-TX{slash}PWM)") (class "Default")
      (node (ref "C6") (pin "1") (pinfunction "1_1") (pintype "passive"))
      (node (ref "R10") (pin "2") (pinfunction "2_2") (pintype "passive"))
      (node (ref "U$1") (pin "3") (pinfunction "3/CAN-TX/PWM_3") (pintype "bidirectional"))
    )
    (net (code "57") (name "Net-(U$1-4{slash}CAN-RX-PWM)") (class "Default")
      (node (ref "SSD1306_OLED37") (pin "4") (pinfunction "4_4") (pintype "passive"))
      (node (ref "U$1") (pin "4") (pinfunction "4/CAN-RX-PWM_4") (pintype "bidirectional"))
    )
    (net (code "58") (name "Net-(U$1-5{slash}PWM)") (class "Default")
      (node (ref "SSD1306_OLED37") (pin "5") (pinfunction "5_5") (pintype "passive"))
      (node (ref "U$1") (pin "5") (pinfunction "5/PWM_5") (pintype "bidirectional"))
    )
    (net (code "59") (name "Net-(U$1-7{slash}RX3)") (class "Default")
      (node (ref "SSD1306_OLED37") (pin "1") (pinfunction "1_1") (pintype "passive"))
      (node (ref "U$1") (pin "7") (pinfunction "7/RX3_7") (pintype "bidirectional"))
    )
    (net (code "60") (name "Net-(U$1-16{slash}A2{slash}T)") (class "Default")
      (node (ref "C9") (pin "2") (pinfunction "2_2") (pintype "passive"))
      (node (ref "R9") (pin "2") (pinfunction "2_2") (pintype "passive"))
      (node (ref "U$1") (pin "16/A2") (pinfunction "16/A2/T_16/A2") (pintype "bidirectional"))
    )
    (net (code "61") (name "Net-(U$1-17{slash}A3{slash}T)") (class "Default")
      (node (ref "C8") (pin "1") (pinfunction "1_1") (pintype "passive"))
      (node (ref "R12") (pin "2") (pinfunction "2_2") (pintype "passive"))
      (node (ref "U$1") (pin "17/A3") (pinfunction "17/A3/T_17/A3") (pintype "bidirectional"))
    )
    (net (code "62") (name "Net-(U$1-21{slash}A7{slash}PWM)") (class "Default")
      (node (ref "R1") (pin "2") (pinfunction "2_2") (pintype "passive"))
      (node (ref "U$1") (pin "21/A7") (pinfunction "21/A7/PWM_21/A7") (pintype "bidirectional"))
    )
    (net (code "63") (name "Net-(U$2-CSNK)") (class "Default")
      (node (ref "R2") (pin "1") (pinfunction "1_1") (pintype "passive"))
      (node (ref "U$2") (pin "5") (pinfunction "CSNK_5") (pintype "bidirectional"))
    )
    (net (code "64") (name "Net-(U$2-CSRC)") (class "Default")
      (node (ref "R3") (pin "1") (pinfunction "1_1") (pintype "passive"))
      (node (ref "U$2") (pin "4") (pinfunction "CSRC_4") (pintype "bidirectional"))
    )
    (net (code "65") (name "Net-(U$3-CSNK)") (class "Default")
      (node (ref "D1") (pin "A") (pinfunction "A_A") (pintype "passive"))
      (node (ref "U$3") (pin "5") (pinfunction "CSNK_5") (pintype "bidirectional"))
      (node (ref "U1") (pin "3") (pinfunction "C_3") (pintype "bidirectional"))
    )
    (net (code "66") (name "Net-(U$3-CSRC)") (class "Default")
      (node (ref "R4") (pin "1") (pinfunction "1_1") (pintype "passive"))
      (node (ref "U$3") (pin "4") (pinfunction "CSRC_4") (pintype "bidirectional"))
    )
    (net (code "67") (name "Net-(U1-A)") (class "Default")
      (node (ref "D1") (pin "C") (pinfunction "C_C") (pintype "passive"))
      (node (ref "R4") (pin "2") (pinfunction "2_2") (pintype "passive"))
      (node (ref "U1") (pin "2") (pinfunction "A_2") (pintype "bidirectional"))
    )
    (net (code "68") (name "VCC") (class "Default")
      (node (ref "C1") (pin "2") (pinfunction "2_2") (pintype "passive"))
      (node (ref "C2") (pin "2") (pinfunction "2_2") (pintype "passive"))
      (node (ref "C3") (pin "2") (pinfunction "2_2") (pintype "passive"))
      (node (ref "C4") (pin "2") (pinfunction "2_2") (pintype "passive"))
      (node (ref "C5") (pin "1") (pinfunction "1_1") (pintype "passive"))
      (node (ref "L1") (pin "1-VDD") (pinfunction "VDD_1-VDD") (pintype "bidirectional"))
      (node (ref "L10") (pin "1-VDD") (pinfunction "VDD_1-VDD") (pintype "bidirectional"))
      (node (ref "L11") (pin "1-VDD") (pinfunction "VDD_1-VDD") (pintype "bidirectional"))
      (node (ref "L12") (pin "1-VDD") (pinfunction "VDD_1-VDD") (pintype "bidirectional"))
      (node (ref "L13") (pin "1-VDD") (pinfunction "VDD_1-VDD") (pintype "bidirectional"))
      (node (ref "L14") (pin "1-VDD") (pinfunction "VDD_1-VDD") (pintype "bidirectional"))
      (node (ref "L15") (pin "1-VDD") (pinfunction "VDD_1-VDD") (pintype "bidirectional"))
      (node (ref "L16") (pin "1-VDD") (pinfunction "VDD_1-VDD") (pintype "bidirectional"))
      (node (ref "L2") (pin "1-VDD") (pinfunction "VDD_1-VDD") (pintype "bidirectional"))
      (node (ref "L3") (pin "1-VDD") (pinfunction "VDD_1-VDD") (pintype "bidirectional"))
      (node (ref "L4") (pin "1-VDD") (pinfunction "VDD_1-VDD") (pintype "bidirectional"))
      (node (ref "L5") (pin "1-VDD") (pinfunction "VDD_1-VDD") (pintype "bidirectional"))
      (node (ref "L6") (pin "1-VDD") (pinfunction "VDD_1-VDD") (pintype "bidirectional"))
      (node (ref "L7") (pin "1-VDD") (pinfunction "VDD_1-VDD") (pintype "bidirectional"))
      (node (ref "L8") (pin "1-VDD") (pinfunction "VDD_1-VDD") (pintype "bidirectional"))
      (node (ref "L9") (pin "1-VDD") (pinfunction "VDD_1-VDD") (pintype "bidirectional"))
      (node (ref "MCP0") (pin "11") (pinfunction "A0_11") (pintype "input"))
      (node (ref "MCP0") (pin "12") (pinfunction "A1_12") (pintype "input"))
      (node (ref "MCP0") (pin "14") (pinfunction "~{RESET}_14") (pintype "input"))
      (node (ref "MCP0") (pin "5") (pinfunction "VDD_5") (pintype "power_in"))
      (node (ref "MCP1") (pin "11") (pinfunction "A0_11") (pintype "input"))
      (node (ref "MCP1") (pin "14") (pinfunction "~{RESET}_14") (pintype "input"))
      (node (ref "MCP1") (pin "5") (pinfunction "VDD_5") (pintype "power_in"))
      (node (ref "R11") (pin "2") (pinfunction "2_2") (pintype "passive"))
      (node (ref "R13") (pin "2") (pinfunction "2_2") (pintype "passive"))
      (node (ref "R3") (pin "2") (pinfunction "2_2") (pintype "passive"))
      (node (ref "R5") (pin "2") (pinfunction "2_2") (pintype "passive"))
      (node (ref "R6") (pin "2") (pinfunction "2_2") (pintype "passive"))
      (node (ref "R8") (pin "2") (pinfunction "2_2") (pintype "passive"))
      (node (ref "SSD1306_OLED37") (pin "7") (pinfunction "7_7") (pintype "passive"))
      (node (ref "U$1") (pin "3.3V") (pinfunction "3.3V_3.3V") (pintype "power_in"))
      (node (ref "U$1") (pin "3.3V1") (pinfunction "3.3V_3.3V1") (pintype "power_in"))
      (node (ref "U1") (pin "8") (pinfunction "VCC_8") (pintype "bidirectional"))
    )
    (net (code "69") (name "unconnected-(L16-DOUT-Pad2-DOUT)") (class "Default")
      (node (ref "L16") (pin "2-DOUT") (pinfunction "DOUT_2-DOUT") (pintype "output"))
    )
    (net (code "70") (name "unconnected-(MCP0-INTA-Pad16)") (class "Default")
      (node (ref "MCP0") (pin "16") (pinfunction "INTA_16") (pintype "output"))
    )
    (net (code "71") (name "unconnected-(MCP0-INTB-Pad15)") (class "Default")
      (node (ref "MCP0") (pin "15") (pinfunction "INTB_15") (pintype "output"))
    )
    (net (code "72") (name "unconnected-(MCP1-GPA7-Pad24)") (class "Default")
      (node (ref "MCP1") (pin "24") (pinfunction "GPA7_24") (pintype "bidirectional"))
    )
    (net (code "73") (name "unconnected-(MCP1-GPB0-Pad25)") (class "Default")
      (node (ref "MCP1") (pin "25") (pinfunction "GPB0_25") (pintype "bidirectional"))
    )
    (net (code "74") (name "unconnected-(MCP1-GPB1-Pad26)") (class "Default")
      (node (ref "MCP1") (pin "26") (pinfunction "GPB1_26") (pintype "bidirectional"))
    )
    (net (code "75") (name "unconnected-(MCP1-GPB2-Pad27)") (class "Default")
      (node (ref "MCP1") (pin "27") (pinfunction "GPB2_27") (pintype "bidirectional"))
    )
    (net (code "76") (name "unconnected-(MCP1-GPB3-Pad28)") (class "Default")
      (node (ref "MCP1") (pin "28") (pinfunction "GPB3_28") (pintype "bidirectional"))
    )
    (net (code "77") (name "unconnected-(MCP1-GPB4-Pad1)") (class "Default")
      (node (ref "MCP1") (pin "1") (pinfunction "GPB4_1") (pintype "bidirectional"))
    )
    (net (code "78") (name "unconnected-(MCP1-GPB5-Pad2)") (class "Default")
      (node (ref "MCP1") (pin "2") (pinfunction "GPB5_2") (pintype "bidirectional"))
    )
    (net (code "79") (name "unconnected-(MCP1-INTA-Pad16)") (class "Default")
      (node (ref "MCP1") (pin "16") (pinfunction "INTA_16") (pintype "output"))
    )
    (net (code "80") (name "unconnected-(MCP1-INTB-Pad15)") (class "Default")
      (node (ref "MCP1") (pin "15") (pinfunction "INTB_15") (pintype "output"))
    )
    (net (code "81") (name "unconnected-(SSD1306_OLED37-Pad3)") (class "Default")
      (node (ref "SSD1306_OLED37") (pin "3") (pinfunction "3_3") (pintype "passive"))
    )
    (net (code "82") (name "unconnected-(SSD1306_OLED37-Pad6)") (class "Default")
      (node (ref "SSD1306_OLED37") (pin "6") (pinfunction "6_6") (pintype "passive"))
    )
    (net (code "83") (name "unconnected-(U$1-6{slash}PWM-Pad6)") (class "Default")
      (node (ref "U$1") (pin "6") (pinfunction "6/PWM_6") (pintype "bidirectional"))
    )
    (net (code "84") (name "unconnected-(U$1-8{slash}TX3-Pad8)") (class "Default")
      (node (ref "U$1") (pin "8") (pinfunction "8/TX3_8") (pintype "bidirectional"))
    )
    (net (code "85") (name "unconnected-(U$1-9{slash}RX2{slash}PWM-Pad9)") (class "Default")
      (node (ref "U$1") (pin "9") (pinfunction "9/RX2/PWM_9") (pintype "bidirectional"))
    )
    (net (code "86") (name "unconnected-(U$1-10{slash}TX2{slash}PWM-Pad10)") (class "Default")
      (node (ref "U$1") (pin "10") (pinfunction "10/TX2/PWM_10") (pintype "bidirectional"))
    )
    (net (code "87") (name "unconnected-(U$1-11{slash}MOSI-Pad11)") (class "Default")
      (node (ref "U$1") (pin "11") (pinfunction "11/MOSI_11") (pintype "bidirectional"))
    )
    (net (code "88") (name "unconnected-(U$1-12{slash}MISO-Pad12)") (class "Default")
      (node (ref "U$1") (pin "12") (pinfunction "12/MISO_12") (pintype "bidirectional"))
    )
    (net (code "89") (name "unconnected-(U$1-13{slash}SCK{slash}LED-Pad13)") (class "Default")
      (node (ref "U$1") (pin "13") (pinfunction "13/SCK/LED_13") (pintype "bidirectional"))
    )
    (net (code "90") (name "unconnected-(U$1-15{slash}A1{slash}T-Pad15{slash}A1)") (class "Default")
      (node (ref "U$1") (pin "15/A1") (pinfunction "15/A1/T_15/A1") (pintype "bidirectional"))
    )
    (net (code "91") (name "unconnected-(U$1-20{slash}A6{slash}PWM-Pad20{slash}A6)") (class "Default")
      (node (ref "U$1") (pin "20/A6") (pinfunction "20/A6/PWM_20/A6") (pintype "bidirectional"))
    )
    (net (code "92") (name "unconnected-(U$1-22{slash}A8{slash}T{slash}PWM-Pad22{slash}A8)") (class "Default")
      (node (ref "U$1") (pin "22/A8") (pinfunction "22/A8/T/PWM_22/A8") (pintype "bidirectional"))
    )
    (net (code "93") (name "unconnected-(U$1-23{slash}A9{slash}T{slash}PWM-Pad23{slash}A9)") (class "Default")
      (node (ref "U$1") (pin "23/A9") (pinfunction "23/A9/T/PWM_23/A9") (pintype "bidirectional"))
    )
    (net (code "94") (name "unconnected-(U$1-A14{slash}DAC-PadA14)") (class "Default")
      (node (ref "U$1") (pin "A14") (pinfunction "A14/DAC_A14") (pintype "bidirectional"))
    )
    (net (code "95") (name "unconnected-(U$1-PadPGM)") (class "Default")
      (node (ref "U$1") (pin "PGM") (pinfunction "PGM_PGM") (pintype "bidirectional"))
    )
    (net (code "96") (name "unconnected-(U$2-NC1-Pad3)") (class "Default")
      (node (ref "U$2") (pin "3") (pinfunction "NC1_3") (pintype "bidirectional"))
    )
    (net (code "97") (name "unconnected-(U$2-NC3-Pad1)") (class "Default")
      (node (ref "U$2") (pin "1") (pinfunction "NC3_1") (pintype "bidirectional"))
    )
    (net (code "98") (name "unconnected-(U$3-GND-Pad2)") (class "Default")
      (node (ref "U$3") (pin "2") (pinfunction "GND_2") (pintype "bidirectional"))
    )
    (net (code "99") (name "unconnected-(U$3-NC1-Pad3)") (class "Default")
      (node (ref "U$3") (pin "3") (pinfunction "NC1_3") (pintype "bidirectional"))
    )
    (net (code "100") (name "unconnected-(U$3-NC3-Pad1)") (class "Default")
      (node (ref "U$3") (pin "1") (pinfunction "NC3_1") (pintype "bidirectional"))
    )
  )
)
